# Nutrient_Management_Control_v2_2.net
KiCad netlist of a schematic drawn in EAGLE
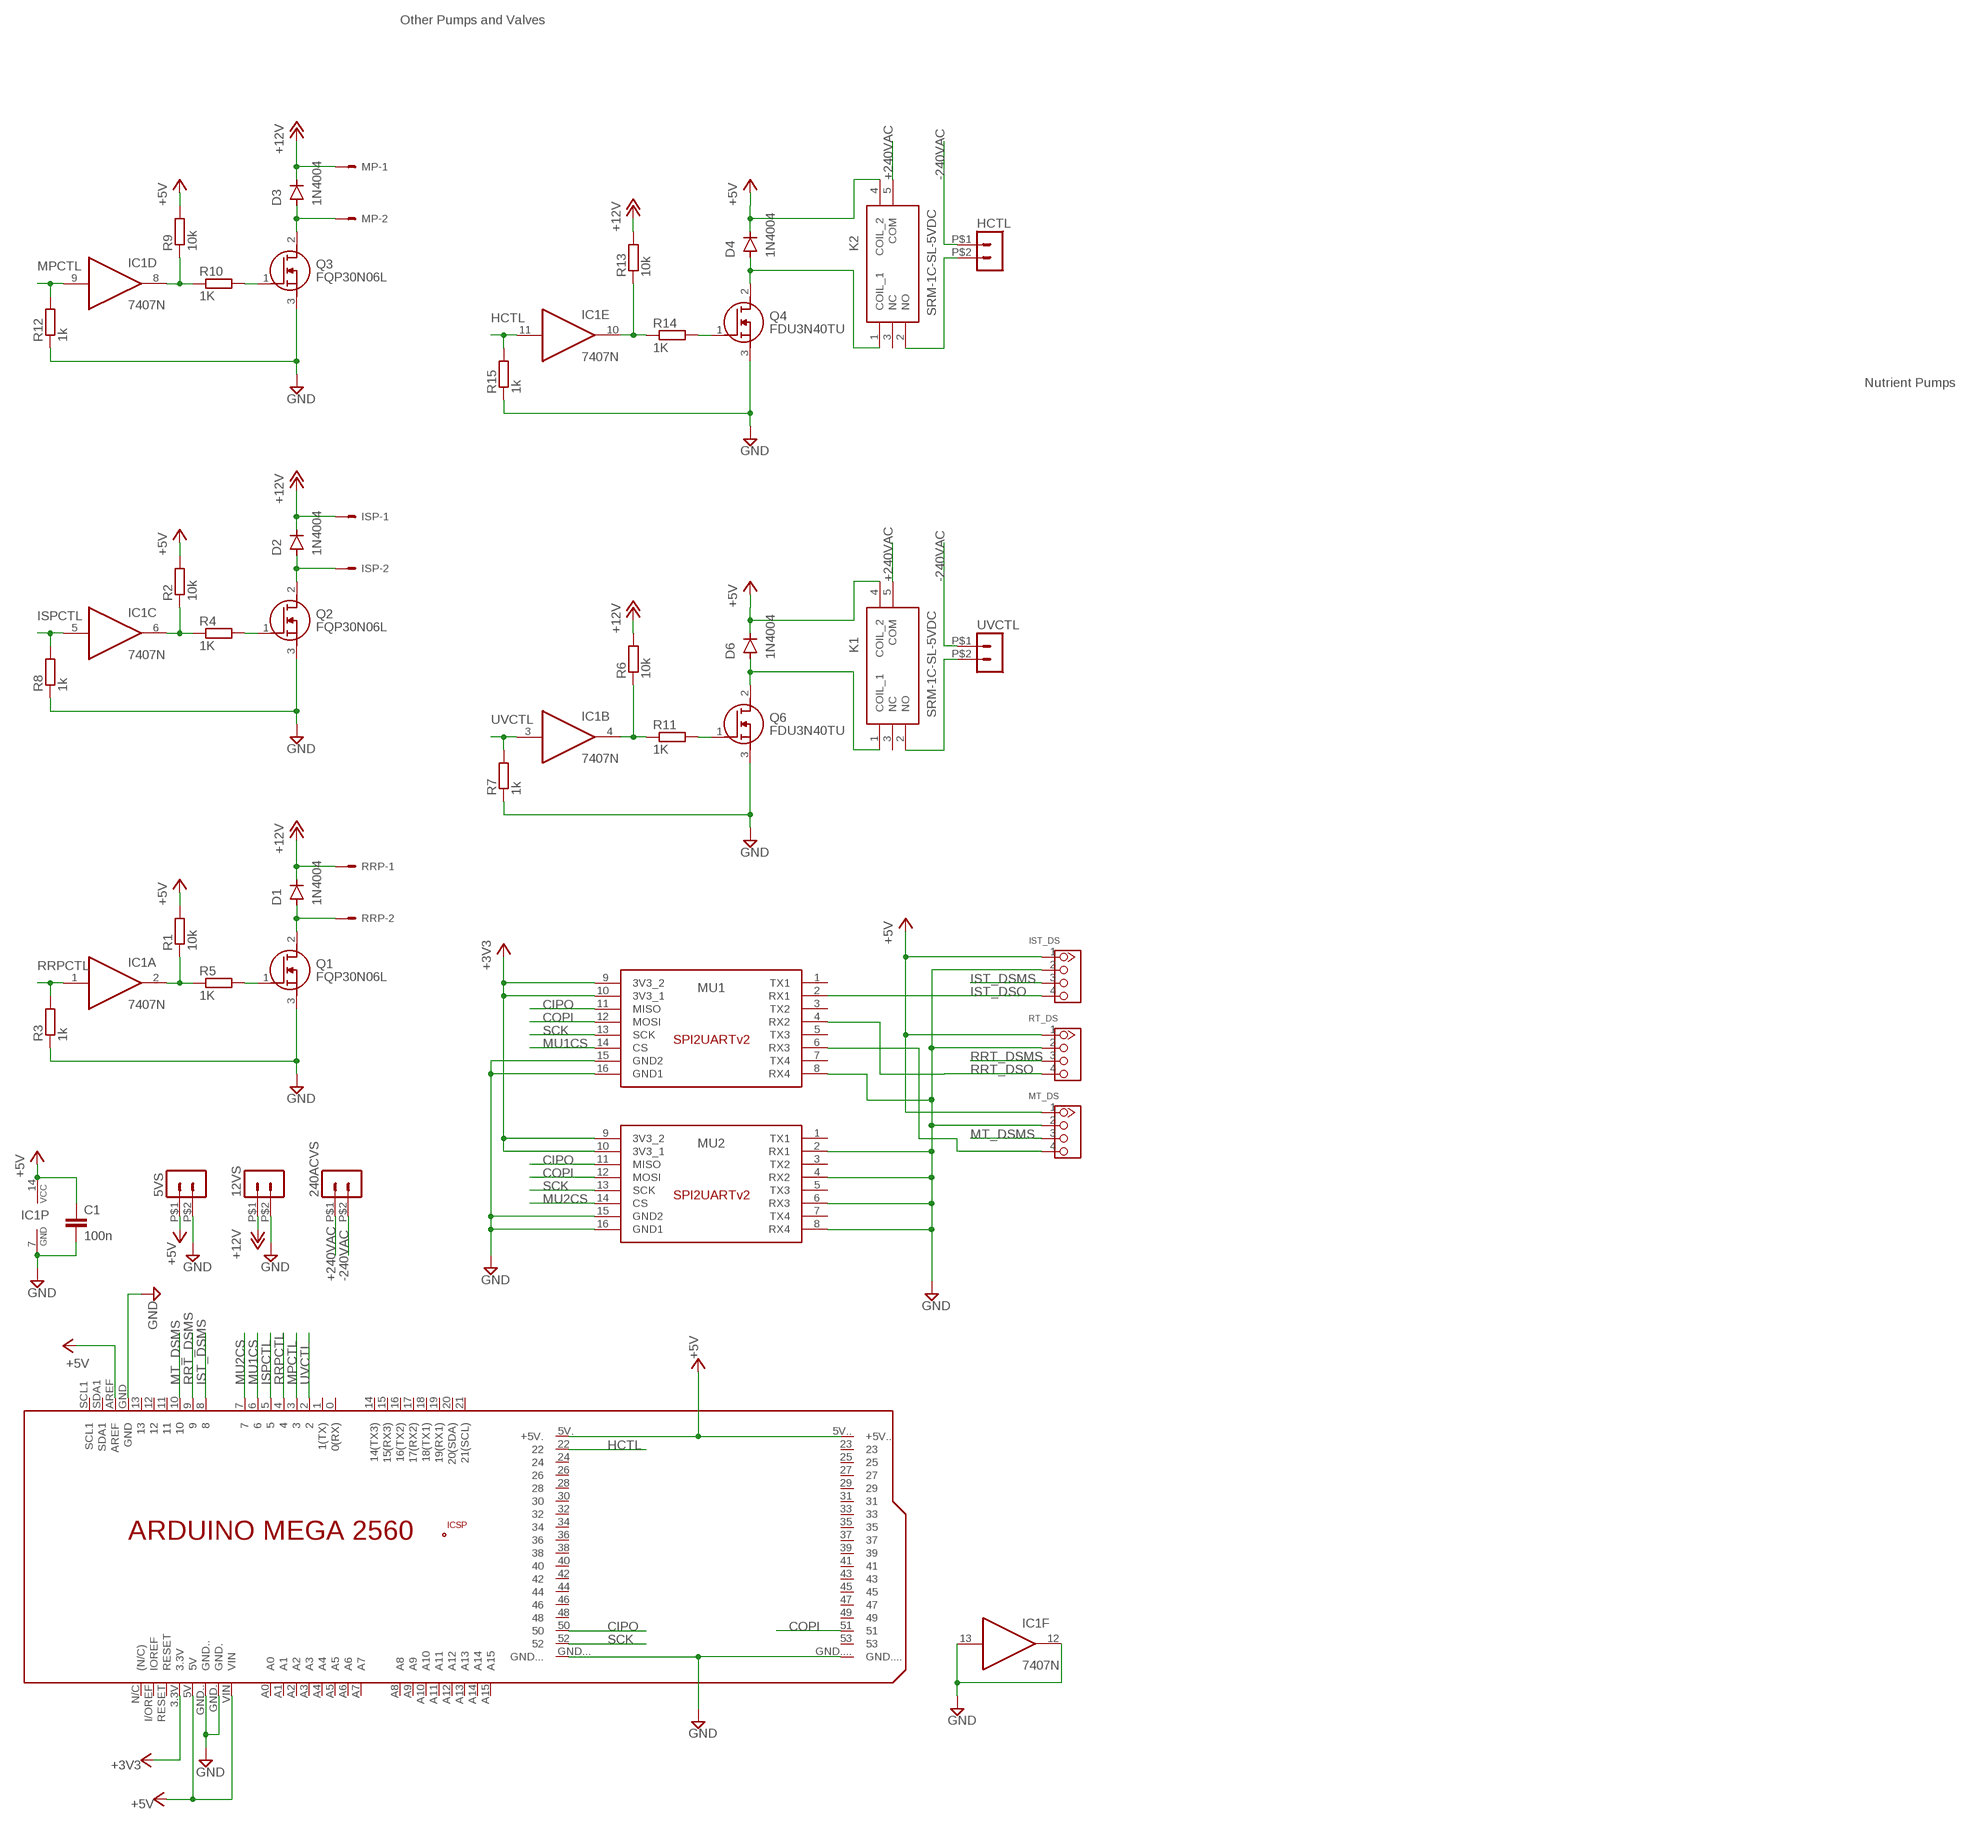
[diagram p0: schematic, sheet 1]

(export (version "E")
  (design (tool "Eeschema 10.0.6"))
  (components
    (comp (ref "5VS")
      (value "HEADER_POS2_43650-0215")
      (footprint "eagle-import:43650-0215")
      (libsource (lib "eagle-import") (part "HEADER_POS2_?43650-0215"))
    )
    (comp (ref "12VS")
      (value "HEADER_POS2_43650-0215")
      (footprint "eagle-import:43650-0215")
      (libsource (lib "eagle-import") (part "HEADER_POS2_?43650-0215"))
    )
    (comp (ref "240ACVS")
      (value "HEADER_POS2_43650-0215")
      (footprint "eagle-import:43650-0215")
      (libsource (lib "eagle-import") (part "HEADER_POS2_?43650-0215"))
    )
    (comp (ref "C1")
      (value "100n")
      (footprint "eagle-import:C050-024X044")
      (libsource (lib "eagle-import") (part "C-EU050-024X044"))
    )
    (comp (ref "D1")
      (value "1N4004")
      (footprint "eagle-import:DO-41")
      (fields
        (field (name "DIGIKEY_PART_NUMBER") "1N4004MSCT-ND")
        (field (name "MANUFACTURER") "Micro Commercial Co")
        (field (name "CREATED_BY") "PCBLayout.com")
      )
      (libsource (lib "eagle-import") (part "1N4004"))
    )
    (comp (ref "D2")
      (value "1N4004")
      (footprint "eagle-import:DO-41")
      (fields
        (field (name "DIGIKEY_PART_NUMBER") "1N4004MSCT-ND")
        (field (name "MANUFACTURER") "Micro Commercial Co")
        (field (name "CREATED_BY") "PCBLayout.com")
      )
      (libsource (lib "eagle-import") (part "1N4004"))
    )
    (comp (ref "D3")
      (value "1N4004")
      (footprint "eagle-import:DO-41")
      (fields
        (field (name "DIGIKEY_PART_NUMBER") "1N4004MSCT-ND")
        (field (name "MANUFACTURER") "Micro Commercial Co")
        (field (name "CREATED_BY") "PCBLayout.com")
      )
      (libsource (lib "eagle-import") (part "1N4004"))
    )
    (comp (ref "D4")
      (value "1N4004")
      (footprint "eagle-import:DO-41")
      (fields
        (field (name "DIGIKEY_PART_NUMBER") "1N4004MSCT-ND")
        (field (name "MANUFACTURER") "Micro Commercial Co")
        (field (name "CREATED_BY") "PCBLayout.com")
      )
      (libsource (lib "eagle-import") (part "1N4004"))
    )
    (comp (ref "D6")
      (value "1N4004")
      (footprint "eagle-import:DO-41")
      (fields
        (field (name "DIGIKEY_PART_NUMBER") "1N4004MSCT-ND")
        (field (name "MANUFACTURER") "Micro Commercial Co")
        (field (name "CREATED_BY") "PCBLayout.com")
      )
      (libsource (lib "eagle-import") (part "1N4004"))
    )
    (comp (ref "HCTL")
      (value "HEADER_POS2_43650-0215")
      (footprint "eagle-import:43650-0215")
      (libsource (lib "eagle-import") (part "HEADER_POS2_?43650-0215"))
    )
    (comp (ref "IC1")
      (value "7407N")
      (footprint "eagle-import:DIL14")
      (libsource (lib "eagle-import") (part "7407N"))
    )
    (comp (ref "ISP")
      (value "JST-XH-02-PIN-LONG-PAD")
      (footprint "eagle-import:JST-XH-02-PACKAGE-LONG-PAD")
      (libsource (lib "eagle-import") (part "JST-XH-02-PIN-LONG-PAD"))
    )
    (comp (ref "IST_DS")
      (value "4P-2.0-90D")
      (footprint "eagle-import:HW4-2.0-90D")
      (libsource (lib "eagle-import") (part "GROVE-CONNECTOR-DIP-90D(4P-2.0)"))
    )
    (comp (ref "K1")
      (value "SRM-1C-SL-5VDC")
      (footprint "eagle-import:SRM1CSL5VDC")
      (libsource (lib "eagle-import") (part "SRM-1C-SL-5VDC"))
    )
    (comp (ref "K2")
      (value "SRM-1C-SL-5VDC")
      (footprint "eagle-import:SRM1CSL5VDC")
      (libsource (lib "eagle-import") (part "SRM-1C-SL-5VDC"))
    )
    (comp (ref "MP")
      (value "JST-XH-02-PIN-LONG-PAD")
      (footprint "eagle-import:JST-XH-02-PACKAGE-LONG-PAD")
      (libsource (lib "eagle-import") (part "JST-XH-02-PIN-LONG-PAD"))
    )
    (comp (ref "MT_DS")
      (value "4P-2.0-90D")
      (footprint "eagle-import:HW4-2.0-90D")
      (libsource (lib "eagle-import") (part "GROVE-CONNECTOR-DIP-90D(4P-2.0)"))
    )
    (comp (ref "MU1")
      (value "SPI2UART_HEADERS")
      (footprint "eagle-import:SPI2UARTV2")
      (libsource (lib "eagle-import") (part "SPI2UART_HEADERS"))
    )
    (comp (ref "MU2")
      (value "SPI2UART_HEADERS")
      (footprint "eagle-import:SPI2UARTV2")
      (libsource (lib "eagle-import") (part "SPI2UART_HEADERS"))
    )
    (comp (ref "PCB2")
      (value "ARDUINO_MEGA2560_SHIELD")
      (footprint "eagle-import:ARDUINO_MEGA2560_SHIELD")
      (libsource (lib "eagle-import") (part "ARDUINO_MEGA2560_SHIELD"))
    )
    (comp (ref "Q1")
      (value "FQP30N06L")
      (footprint "eagle-import:TO254P470X1016X2019-3P")
      (fields (field (name "RS_PART_NUMBER") "8075863P"))
      (libsource (lib "eagle-import") (part "FQP30N06L"))
    )
    (comp (ref "Q2")
      (value "FQP30N06L")
      (footprint "eagle-import:TO254P470X1016X2019-3P")
      (fields (field (name "RS_PART_NUMBER") "8075863P"))
      (libsource (lib "eagle-import") (part "FQP30N06L"))
    )
    (comp (ref "Q3")
      (value "FQP30N06L")
      (footprint "eagle-import:TO254P470X1016X2019-3P")
      (fields (field (name "RS_PART_NUMBER") "8075863P"))
      (libsource (lib "eagle-import") (part "FQP30N06L"))
    )
    (comp (ref "Q4")
      (value "FDU3N40TU")
      (footprint "eagle-import:TO229P250X658X985-3P")
      (fields (field (name "RS_PART_NUMBER") "8070701P"))
      (libsource (lib "eagle-import") (part "FDU3N40TU"))
    )
    (comp (ref "Q6")
      (value "FDU3N40TU")
      (footprint "eagle-import:TO229P250X658X985-3P")
      (fields (field (name "RS_PART_NUMBER") "8070701P"))
      (libsource (lib "eagle-import") (part "FDU3N40TU"))
    )
    (comp (ref "R1")
      (value "10k")
      (footprint "eagle-import:0204_7")
      (libsource (lib "eagle-import") (part "R-EU_0204/7"))
    )
    (comp (ref "R2")
      (value "10k")
      (footprint "eagle-import:0204_7")
      (libsource (lib "eagle-import") (part "R-EU_0204/7"))
    )
    (comp (ref "R3")
      (value "1k")
      (footprint "eagle-import:0204_7")
      (libsource (lib "eagle-import") (part "R-EU_0204/7"))
    )
    (comp (ref "R4")
      (value "1K")
      (footprint "eagle-import:0204_7")
      (libsource (lib "eagle-import") (part "R-EU_0204/7"))
    )
    (comp (ref "R5")
      (value "1K")
      (footprint "eagle-import:0204_7")
      (libsource (lib "eagle-import") (part "R-EU_0204/7"))
    )
    (comp (ref "R6")
      (value "10k")
      (footprint "eagle-import:0204_7")
      (libsource (lib "eagle-import") (part "R-EU_0204/7"))
    )
    (comp (ref "R7")
      (value "1k")
      (footprint "eagle-import:0204_7")
      (libsource (lib "eagle-import") (part "R-EU_0204/7"))
    )
    (comp (ref "R8")
      (value "1k")
      (footprint "eagle-import:0204_7")
      (libsource (lib "eagle-import") (part "R-EU_0204/7"))
    )
    (comp (ref "R9")
      (value "10k")
      (footprint "eagle-import:0204_7")
      (libsource (lib "eagle-import") (part "R-EU_0204/7"))
    )
    (comp (ref "R10")
      (value "1K")
      (footprint "eagle-import:0204_7")
      (libsource (lib "eagle-import") (part "R-EU_0204/7"))
    )
    (comp (ref "R11")
      (value "1K")
      (footprint "eagle-import:0204_7")
      (libsource (lib "eagle-import") (part "R-EU_0204/7"))
    )
    (comp (ref "R12")
      (value "1k")
      (footprint "eagle-import:0204_7")
      (libsource (lib "eagle-import") (part "R-EU_0204/7"))
    )
    (comp (ref "R13")
      (value "10k")
      (footprint "eagle-import:0204_7")
      (libsource (lib "eagle-import") (part "R-EU_0204/7"))
    )
    (comp (ref "R14")
      (value "1K")
      (footprint "eagle-import:0204_7")
      (libsource (lib "eagle-import") (part "R-EU_0204/7"))
    )
    (comp (ref "R15")
      (value "1k")
      (footprint "eagle-import:0204_7")
      (libsource (lib "eagle-import") (part "R-EU_0204/7"))
    )
    (comp (ref "RRP")
      (value "JST-XH-02-PIN-LONG-PAD")
      (footprint "eagle-import:JST-XH-02-PACKAGE-LONG-PAD")
      (libsource (lib "eagle-import") (part "JST-XH-02-PIN-LONG-PAD"))
    )
    (comp (ref "RT_DS")
      (value "4P-2.0-90D")
      (footprint "eagle-import:HW4-2.0-90D")
      (libsource (lib "eagle-import") (part "GROVE-CONNECTOR-DIP-90D(4P-2.0)"))
    )
    (comp (ref "UVCTL")
      (value "HEADER_POS2_43650-0215")
      (footprint "eagle-import:43650-0215")
      (libsource (lib "eagle-import") (part "HEADER_POS2_?43650-0215"))
    )
  )
  (nets
    (net (code "1") (name "+3V3") (class "Default")
      (node (ref "MU1") (pin "10") (pinfunction "3V3_1_10") (pintype "power_in"))
      (node (ref "MU1") (pin "9") (pinfunction "3V3_2_9") (pintype "power_in"))
      (node (ref "MU2") (pin "10") (pinfunction "3V3_1_10") (pintype "power_in"))
      (node (ref "MU2") (pin "9") (pinfunction "3V3_2_9") (pintype "power_in"))
      (node (ref "PCB2") (pin "3.3V") (pinfunction "3.3V_3.3V") (pintype "bidirectional"))
    )
    (net (code "2") (name "+5V") (class "Default")
      (node (ref "5VS") (pin "P$1") (pinfunction "1_P$1") (pintype "passive"))
      (node (ref "C1") (pin "1") (pinfunction "1_1") (pintype "passive"))
      (node (ref "D4") (pin "C") (pinfunction "C_C") (pintype "passive"))
      (node (ref "D6") (pin "C") (pinfunction "C_C") (pintype "passive"))
      (node (ref "IC1") (pin "14") (pinfunction "VCC_14") (pintype "power_in"))
      (node (ref "IST_DS") (pin "1") (pinfunction "1_1") (pintype "bidirectional"))
      (node (ref "K1") (pin "4") (pinfunction "COIL_2_4") (pintype "bidirectional"))
      (node (ref "K2") (pin "4") (pinfunction "COIL_2_4") (pintype "bidirectional"))
      (node (ref "MT_DS") (pin "1") (pinfunction "1_1") (pintype "bidirectional"))
      (node (ref "PCB2") (pin "5V") (pinfunction "5V_5V") (pintype "bidirectional"))
      (node (ref "PCB2") (pin "5V.") (pinfunction "+5V._5V.") (pintype "bidirectional"))
      (node (ref "PCB2") (pin "5V..") (pinfunction "+5V.._5V..") (pintype "bidirectional"))
      (node (ref "PCB2") (pin "AREF") (pinfunction "AREF_AREF") (pintype "bidirectional"))
      (node (ref "PCB2") (pin "VIN") (pinfunction "VIN_VIN") (pintype "bidirectional"))
      (node (ref "R1") (pin "2") (pinfunction "2_2") (pintype "passive"))
      (node (ref "R2") (pin "2") (pinfunction "2_2") (pintype "passive"))
      (node (ref "R9") (pin "2") (pinfunction "2_2") (pintype "passive"))
      (node (ref "RT_DS") (pin "1") (pinfunction "1_1") (pintype "bidirectional"))
    )
    (net (code "3") (name "+12V") (class "Default")
      (node (ref "12VS") (pin "P$1") (pinfunction "1_P$1") (pintype "passive"))
      (node (ref "D1") (pin "C") (pinfunction "C_C") (pintype "passive"))
      (node (ref "D2") (pin "C") (pinfunction "C_C") (pintype "passive"))
      (node (ref "D3") (pin "C") (pinfunction "C_C") (pintype "passive"))
      (node (ref "ISP") (pin "1") (pinfunction "S_1") (pintype "passive"))
      (node (ref "MP") (pin "1") (pinfunction "S_1") (pintype "passive"))
      (node (ref "R13") (pin "2") (pinfunction "2_2") (pintype "passive"))
      (node (ref "R6") (pin "2") (pinfunction "2_2") (pintype "passive"))
      (node (ref "RRP") (pin "1") (pinfunction "S_1") (pintype "passive"))
    )
    (net (code "4") (name "/+240VAC") (class "Default")
      (node (ref "240ACVS") (pin "P$1") (pinfunction "1_P$1") (pintype "passive"))
      (node (ref "K1") (pin "5") (pinfunction "COM_5") (pintype "bidirectional"))
      (node (ref "K2") (pin "5") (pinfunction "COM_5") (pintype "bidirectional"))
    )
    (net (code "5") (name "/-240VAC") (class "Default")
      (node (ref "240ACVS") (pin "P$2") (pinfunction "2_P$2") (pintype "passive"))
      (node (ref "HCTL") (pin "P$1") (pinfunction "1_P$1") (pintype "passive"))
      (node (ref "UVCTL") (pin "P$1") (pinfunction "1_P$1") (pintype "passive"))
    )
    (net (code "6") (name "/CIPO") (class "Default")
      (node (ref "MU1") (pin "11") (pinfunction "MISO_11") (pintype "output"))
      (node (ref "MU2") (pin "11") (pinfunction "MISO_11") (pintype "output"))
      (node (ref "PCB2") (pin "50") (pinfunction "50_50") (pintype "bidirectional"))
    )
    (net (code "7") (name "/COPI") (class "Default")
      (node (ref "MU1") (pin "12") (pinfunction "MOSI_12") (pintype "input"))
      (node (ref "MU2") (pin "12") (pinfunction "MOSI_12") (pintype "input"))
      (node (ref "PCB2") (pin "51") (pinfunction "51_51") (pintype "bidirectional"))
    )
    (net (code "8") (name "/HCTL") (class "Default")
      (node (ref "IC1") (pin "11") (pinfunction "I_11") (pintype "input"))
      (node (ref "PCB2") (pin "22") (pinfunction "22_22") (pintype "bidirectional"))
      (node (ref "R15") (pin "2") (pinfunction "2_2") (pintype "passive"))
    )
    (net (code "9") (name "/ISPCTL") (class "Default")
      (node (ref "IC1") (pin "5") (pinfunction "I_5") (pintype "input"))
      (node (ref "PCB2") (pin "5") (pinfunction "5_5") (pintype "bidirectional"))
      (node (ref "R8") (pin "2") (pinfunction "2_2") (pintype "passive"))
    )
    (net (code "10") (name "/IST_DSMS") (class "Default")
      (node (ref "IST_DS") (pin "3") (pinfunction "3_3") (pintype "bidirectional"))
      (node (ref "PCB2") (pin "8") (pinfunction "8_8") (pintype "bidirectional"))
    )
    (net (code "11") (name "/IST_DSO") (class "Default")
      (node (ref "IST_DS") (pin "4") (pinfunction "4_4") (pintype "bidirectional"))
      (node (ref "MU1") (pin "2") (pinfunction "RX1_2") (pintype "input"))
    )
    (net (code "12") (name "/MPCTL") (class "Default")
      (node (ref "IC1") (pin "9") (pinfunction "I_9") (pintype "input"))
      (node (ref "PCB2") (pin "3") (pinfunction "3_3") (pintype "bidirectional"))
      (node (ref "R12") (pin "2") (pinfunction "2_2") (pintype "passive"))
    )
    (net (code "13") (name "/MT_DSMS") (class "Default")
      (node (ref "MT_DS") (pin "3") (pinfunction "3_3") (pintype "bidirectional"))
      (node (ref "PCB2") (pin "10") (pinfunction "10_10") (pintype "bidirectional"))
    )
    (net (code "14") (name "/MU1CS") (class "Default")
      (node (ref "MU1") (pin "14") (pinfunction "CS_14") (pintype "input"))
      (node (ref "PCB2") (pin "6") (pinfunction "6_6") (pintype "bidirectional"))
    )
    (net (code "15") (name "/MU2CS") (class "Default")
      (node (ref "MU2") (pin "14") (pinfunction "CS_14") (pintype "input"))
      (node (ref "PCB2") (pin "7") (pinfunction "7_7") (pintype "bidirectional"))
    )
    (net (code "16") (name "/RRPCTL") (class "Default")
      (node (ref "IC1") (pin "1") (pinfunction "I_1") (pintype "input"))
      (node (ref "PCB2") (pin "4") (pinfunction "4_4") (pintype "bidirectional"))
      (node (ref "R3") (pin "2") (pinfunction "2_2") (pintype "passive"))
    )
    (net (code "17") (name "/RRT_DSMS") (class "Default")
      (node (ref "PCB2") (pin "9") (pinfunction "9_9") (pintype "bidirectional"))
      (node (ref "RT_DS") (pin "3") (pinfunction "3_3") (pintype "bidirectional"))
    )
    (net (code "18") (name "/RRT_DSO") (class "Default")
      (node (ref "MU1") (pin "4") (pinfunction "RX2_4") (pintype "input"))
      (node (ref "RT_DS") (pin "4") (pinfunction "4_4") (pintype "bidirectional"))
    )
    (net (code "19") (name "/SCK") (class "Default")
      (node (ref "MU1") (pin "13") (pinfunction "SCK_13") (pintype "input"))
      (node (ref "MU2") (pin "13") (pinfunction "SCK_13") (pintype "input"))
      (node (ref "PCB2") (pin "52") (pinfunction "52_52") (pintype "bidirectional"))
    )
    (net (code "20") (name "/UVCTL") (class "Default")
      (node (ref "IC1") (pin "3") (pinfunction "I_3") (pintype "input"))
      (node (ref "PCB2") (pin "2") (pinfunction "2_2") (pintype "bidirectional"))
      (node (ref "R7") (pin "2") (pinfunction "2_2") (pintype "passive"))
    )
    (net (code "21") (name "GND") (class "Default")
      (node (ref "12VS") (pin "P$2") (pinfunction "2_P$2") (pintype "passive"))
      (node (ref "5VS") (pin "P$2") (pinfunction "2_P$2") (pintype "passive"))
      (node (ref "C1") (pin "2") (pinfunction "2_2") (pintype "passive"))
      (node (ref "IC1") (pin "12") (pinfunction "O_12") (pintype "open_collector"))
      (node (ref "IC1") (pin "13") (pinfunction "I_13") (pintype "input"))
      (node (ref "IC1") (pin "7") (pinfunction "GND_7") (pintype "power_in"))
      (node (ref "IST_DS") (pin "2") (pinfunction "2_2") (pintype "bidirectional"))
      (node (ref "MT_DS") (pin "2") (pinfunction "2_2") (pintype "bidirectional"))
      (node (ref "MU1") (pin "15") (pinfunction "GND2_15") (pintype "power_in"))
      (node (ref "MU1") (pin "16") (pinfunction "GND1_16") (pintype "power_in"))
      (node (ref "MU1") (pin "8") (pinfunction "RX4_8") (pintype "input"))
      (node (ref "MU2") (pin "15") (pinfunction "GND2_15") (pintype "power_in"))
      (node (ref "MU2") (pin "16") (pinfunction "GND1_16") (pintype "power_in"))
      (node (ref "MU2") (pin "2") (pinfunction "RX1_2") (pintype "input"))
      (node (ref "MU2") (pin "4") (pinfunction "RX2_4") (pintype "input"))
      (node (ref "MU2") (pin "6") (pinfunction "RX3_6") (pintype "input"))
      (node (ref "MU2") (pin "8") (pinfunction "RX4_8") (pintype "input"))
      (node (ref "PCB2") (pin "GND") (pinfunction "GND_GND") (pintype "bidirectional"))
      (node (ref "PCB2") (pin "GND.") (pinfunction "GND._GND.") (pintype "bidirectional"))
      (node (ref "PCB2") (pin "GND..") (pinfunction "GND.._GND..") (pintype "bidirectional"))
      (node (ref "PCB2") (pin "GND...") (pinfunction "GND..._GND...") (pintype "bidirectional"))
      (node (ref "PCB2") (pin "GND....") (pinfunction "GND...._GND....") (pintype "bidirectional"))
      (node (ref "Q1") (pin "3") (pinfunction "S_3") (pintype "bidirectional"))
      (node (ref "Q2") (pin "3") (pinfunction "S_3") (pintype "bidirectional"))
      (node (ref "Q3") (pin "3") (pinfunction "S_3") (pintype "bidirectional"))
      (node (ref "Q4") (pin "3") (pinfunction "S_3") (pintype "bidirectional"))
      (node (ref "Q6") (pin "3") (pinfunction "S_3") (pintype "bidirectional"))
      (node (ref "R12") (pin "1") (pinfunction "1_1") (pintype "passive"))
      (node (ref "R15") (pin "1") (pinfunction "1_1") (pintype "passive"))
      (node (ref "R3") (pin "1") (pinfunction "1_1") (pintype "passive"))
      (node (ref "R7") (pin "1") (pinfunction "1_1") (pintype "passive"))
      (node (ref "R8") (pin "1") (pinfunction "1_1") (pintype "passive"))
      (node (ref "RT_DS") (pin "2") (pinfunction "2_2") (pintype "bidirectional"))
    )
    (net (code "22") (name "Net-(HCTL-2)") (class "Default")
      (node (ref "HCTL") (pin "P$2") (pinfunction "2_P$2") (pintype "passive"))
      (node (ref "K2") (pin "2") (pinfunction "NO_2") (pintype "bidirectional"))
    )
    (net (code "23") (name "Net-(IC1A-O)") (class "Default")
      (node (ref "IC1") (pin "2") (pinfunction "O_2") (pintype "open_collector"))
      (node (ref "R1") (pin "1") (pinfunction "1_1") (pintype "passive"))
      (node (ref "R5") (pin "1") (pinfunction "1_1") (pintype "passive"))
    )
    (net (code "24") (name "Net-(IC1B-O)") (class "Default")
      (node (ref "IC1") (pin "4") (pinfunction "O_4") (pintype "open_collector"))
      (node (ref "R11") (pin "1") (pinfunction "1_1") (pintype "passive"))
      (node (ref "R6") (pin "1") (pinfunction "1_1") (pintype "passive"))
    )
    (net (code "25") (name "Net-(IC1C-O)") (class "Default")
      (node (ref "IC1") (pin "6") (pinfunction "O_6") (pintype "open_collector"))
      (node (ref "R2") (pin "1") (pinfunction "1_1") (pintype "passive"))
      (node (ref "R4") (pin "1") (pinfunction "1_1") (pintype "passive"))
    )
    (net (code "26") (name "Net-(IC1D-O)") (class "Default")
      (node (ref "IC1") (pin "8") (pinfunction "O_8") (pintype "open_collector"))
      (node (ref "R10") (pin "1") (pinfunction "1_1") (pintype "passive"))
      (node (ref "R9") (pin "1") (pinfunction "1_1") (pintype "passive"))
    )
    (net (code "27") (name "Net-(IC1E-O)") (class "Default")
      (node (ref "IC1") (pin "10") (pinfunction "O_10") (pintype "open_collector"))
      (node (ref "R13") (pin "1") (pinfunction "1_1") (pintype "passive"))
      (node (ref "R14") (pin "1") (pinfunction "1_1") (pintype "passive"))
    )
    (net (code "28") (name "Net-(ISPB-S)") (class "Default")
      (node (ref "D2") (pin "A") (pinfunction "A_A") (pintype "passive"))
      (node (ref "ISP") (pin "2") (pinfunction "S_2") (pintype "passive"))
      (node (ref "Q2") (pin "2") (pinfunction "D_2") (pintype "bidirectional"))
    )
    (net (code "29") (name "Net-(K1-COIL_1)") (class "Default")
      (node (ref "D6") (pin "A") (pinfunction "A_A") (pintype "passive"))
      (node (ref "K1") (pin "1") (pinfunction "COIL_1_1") (pintype "bidirectional"))
      (node (ref "Q6") (pin "2") (pinfunction "D_2") (pintype "bidirectional"))
    )
    (net (code "30") (name "Net-(K1-NO)") (class "Default")
      (node (ref "K1") (pin "2") (pinfunction "NO_2") (pintype "bidirectional"))
      (node (ref "UVCTL") (pin "P$2") (pinfunction "2_P$2") (pintype "passive"))
    )
    (net (code "31") (name "Net-(K2-COIL_1)") (class "Default")
      (node (ref "D4") (pin "A") (pinfunction "A_A") (pintype "passive"))
      (node (ref "K2") (pin "1") (pinfunction "COIL_1_1") (pintype "bidirectional"))
      (node (ref "Q4") (pin "2") (pinfunction "D_2") (pintype "bidirectional"))
    )
    (net (code "32") (name "Net-(MPB-S)") (class "Default")
      (node (ref "D3") (pin "A") (pinfunction "A_A") (pintype "passive"))
      (node (ref "MP") (pin "2") (pinfunction "S_2") (pintype "passive"))
      (node (ref "Q3") (pin "2") (pinfunction "D_2") (pintype "bidirectional"))
    )
    (net (code "33") (name "Net-(MU1-RX3)") (class "Default")
      (node (ref "MT_DS") (pin "4") (pinfunction "4_4") (pintype "bidirectional"))
      (node (ref "MU1") (pin "6") (pinfunction "RX3_6") (pintype "input"))
    )
    (net (code "34") (name "Net-(Q1-D)") (class "Default")
      (node (ref "D1") (pin "A") (pinfunction "A_A") (pintype "passive"))
      (node (ref "Q1") (pin "2") (pinfunction "D_2") (pintype "bidirectional"))
      (node (ref "RRP") (pin "2") (pinfunction "S_2") (pintype "passive"))
    )
    (net (code "35") (name "Net-(Q1-G)") (class "Default")
      (node (ref "Q1") (pin "1") (pinfunction "G_1") (pintype "bidirectional"))
      (node (ref "R5") (pin "2") (pinfunction "2_2") (pintype "passive"))
    )
    (net (code "36") (name "Net-(Q2-G)") (class "Default")
      (node (ref "Q2") (pin "1") (pinfunction "G_1") (pintype "bidirectional"))
      (node (ref "R4") (pin "2") (pinfunction "2_2") (pintype "passive"))
    )
    (net (code "37") (name "Net-(Q3-G)") (class "Default")
      (node (ref "Q3") (pin "1") (pinfunction "G_1") (pintype "bidirectional"))
      (node (ref "R10") (pin "2") (pinfunction "2_2") (pintype "passive"))
    )
    (net (code "38") (name "Net-(Q4-G)") (class "Default")
      (node (ref "Q4") (pin "1") (pinfunction "G_1") (pintype "bidirectional"))
      (node (ref "R14") (pin "2") (pinfunction "2_2") (pintype "passive"))
    )
    (net (code "39") (name "Net-(Q6-G)") (class "Default")
      (node (ref "Q6") (pin "1") (pinfunction "G_1") (pintype "bidirectional"))
      (node (ref "R11") (pin "2") (pinfunction "2_2") (pintype "passive"))
    )
    (net (code "40") (name "unconnected-(K1-NC-Pad3)") (class "Default")
      (node (ref "K1") (pin "3") (pinfunction "NC_3") (pintype "no_connect"))
    )
    (net (code "41") (name "unconnected-(K2-NC-Pad3)") (class "Default")
      (node (ref "K2") (pin "3") (pinfunction "NC_3") (pintype "no_connect"))
    )
    (net (code "42") (name "unconnected-(MU1-TX1-Pad1)") (class "Default")
      (node (ref "MU1") (pin "1") (pinfunction "TX1_1") (pintype "output"))
    )
    (net (code "43") (name "unconnected-(MU1-TX2-Pad3)") (class "Default")
      (node (ref "MU1") (pin "3") (pinfunction "TX2_3") (pintype "output"))
    )
    (net (code "44") (name "unconnected-(MU1-TX3-Pad5)") (class "Default")
      (node (ref "MU1") (pin "5") (pinfunction "TX3_5") (pintype "output"))
    )
    (net (code "45") (name "unconnected-(MU1-TX4-Pad7)") (class "Default")
      (node (ref "MU1") (pin "7") (pinfunction "TX4_7") (pintype "output"))
    )
    (net (code "46") (name "unconnected-(MU2-TX1-Pad1)") (class "Default")
      (node (ref "MU2") (pin "1") (pinfunction "TX1_1") (pintype "output"))
    )
    (net (code "47") (name "unconnected-(MU2-TX2-Pad3)") (class "Default")
      (node (ref "MU2") (pin "3") (pinfunction "TX2_3") (pintype "output"))
    )
    (net (code "48") (name "unconnected-(MU2-TX3-Pad5)") (class "Default")
      (node (ref "MU2") (pin "5") (pinfunction "TX3_5") (pintype "output"))
    )
    (net (code "49") (name "unconnected-(MU2-TX4-Pad7)") (class "Default")
      (node (ref "MU2") (pin "7") (pinfunction "TX4_7") (pintype "output"))
    )
    (net (code "50") (name "unconnected-(PCB2-(N{slash}C)-PadN{slash}C)") (class "Default")
      (node (ref "PCB2") (pin "N/C") (pinfunction "(N/C)_N/C") (pintype "bidirectional"))
    )
    (net (code "51") (name "unconnected-(PCB2-0(RX)-Pad0)") (class "Default")
      (node (ref "PCB2") (pin "0") (pinfunction "0(RX)_0") (pintype "bidirectional"))
    )
    (net (code "52") (name "unconnected-(PCB2-1(TX)-Pad1)") (class "Default")
      (node (ref "PCB2") (pin "1") (pinfunction "1(TX)_1") (pintype "bidirectional"))
    )
    (net (code "53") (name "unconnected-(PCB2-14(TX3)-Pad14)") (class "Default")
      (node (ref "PCB2") (pin "14") (pinfunction "14(TX3)_14") (pintype "bidirectional"))
    )
    (net (code "54") (name "unconnected-(PCB2-15(RX3)-Pad15)") (class "Default")
      (node (ref "PCB2") (pin "15") (pinfunction "15(RX3)_15") (pintype "bidirectional"))
    )
    (net (code "55") (name "unconnected-(PCB2-16(TX2)-Pad16)") (class "Default")
      (node (ref "PCB2") (pin "16") (pinfunction "16(TX2)_16") (pintype "bidirectional"))
    )
    (net (code "56") (name "unconnected-(PCB2-17(RX2)-Pad17)") (class "Default")
      (node (ref "PCB2") (pin "17") (pinfunction "17(RX2)_17") (pintype "bidirectional"))
    )
    (net (code "57") (name "unconnected-(PCB2-18(TX1)-Pad18)") (class "Default")
      (node (ref "PCB2") (pin "18") (pinfunction "18(TX1)_18") (pintype "bidirectional"))
    )
    (net (code "58") (name "unconnected-(PCB2-19(RX1)-Pad19)") (class "Default")
      (node (ref "PCB2") (pin "19") (pinfunction "19(RX1)_19") (pintype "bidirectional"))
    )
    (net (code "59") (name "unconnected-(PCB2-20(SDA)-Pad20)") (class "Default")
      (node (ref "PCB2") (pin "20") (pinfunction "20(SDA)_20") (pintype "bidirectional"))
    )
    (net (code "60") (name "unconnected-(PCB2-21(SCL)-Pad21)") (class "Default")
      (node (ref "PCB2") (pin "21") (pinfunction "21(SCL)_21") (pintype "bidirectional"))
    )
    (net (code "61") (name "unconnected-(PCB2-IOREF-PadI{slash}OREF)") (class "Default")
      (node (ref "PCB2") (pin "I/OREF") (pinfunction "IOREF_I/OREF") (pintype "bidirectional"))
    )
    (net (code "62") (name "unconnected-(PCB2-Pad+5V_)") (class "Default")
      (node (ref "PCB2") (pin "+5V_") (pinfunction "+5V__+5V_") (pintype "bidirectional"))
    )
    (net (code "63") (name "unconnected-(PCB2-Pad11)") (class "Default")
      (node (ref "PCB2") (pin "11") (pinfunction "11_11") (pintype "bidirectional"))
    )
    (net (code "64") (name "unconnected-(PCB2-Pad12)") (class "Default")
      (node (ref "PCB2") (pin "12") (pinfunction "12_12") (pintype "bidirectional"))
    )
    (net (code "65") (name "unconnected-(PCB2-Pad13)") (class "Default")
      (node (ref "PCB2") (pin "13") (pinfunction "13_13") (pintype "bidirectional"))
    )
    (net (code "66") (name "unconnected-(PCB2-Pad23)") (class "Default")
      (node (ref "PCB2") (pin "23") (pinfunction "23_23") (pintype "bidirectional"))
    )
    (net (code "67") (name "unconnected-(PCB2-Pad24)") (class "Default")
      (node (ref "PCB2") (pin "24") (pinfunction "24_24") (pintype "bidirectional"))
    )
    (net (code "68") (name "unconnected-(PCB2-Pad25)") (class "Default")
      (node (ref "PCB2") (pin "25") (pinfunction "25_25") (pintype "bidirectional"))
    )
    (net (code "69") (name "unconnected-(PCB2-Pad26)") (class "Default")
      (node (ref "PCB2") (pin "26") (pinfunction "26_26") (pintype "bidirectional"))
    )
    (net (code "70") (name "unconnected-(PCB2-Pad27)") (class "Default")
      (node (ref "PCB2") (pin "27") (pinfunction "27_27") (pintype "bidirectional"))
    )
    (net (code "71") (name "unconnected-(PCB2-Pad28)") (class "Default")
      (node (ref "PCB2") (pin "28") (pinfunction "28_28") (pintype "bidirectional"))
    )
    (net (code "72") (name "unconnected-(PCB2-Pad29)") (class "Default")
      (node (ref "PCB2") (pin "29") (pinfunction "29_29") (pintype "bidirectional"))
    )
    (net (code "73") (name "unconnected-(PCB2-Pad30)") (class "Default")
      (node (ref "PCB2") (pin "30") (pinfunction "30_30") (pintype "bidirectional"))
    )
    (net (code "74") (name "unconnected-(PCB2-Pad31)") (class "Default")
      (node (ref "PCB2") (pin "31") (pinfunction "31_31") (pintype "bidirectional"))
    )
    (net (code "75") (name "unconnected-(PCB2-Pad32)") (class "Default")
      (node (ref "PCB2") (pin "32") (pinfunction "32_32") (pintype "bidirectional"))
    )
    (net (code "76") (name "unconnected-(PCB2-Pad33)") (class "Default")
      (node (ref "PCB2") (pin "33") (pinfunction "33_33") (pintype "bidirectional"))
    )
    (net (code "77") (name "unconnected-(PCB2-Pad34)") (class "Default")
      (node (ref "PCB2") (pin "34") (pinfunction "34_34") (pintype "bidirectional"))
    )
    (net (code "78") (name "unconnected-(PCB2-Pad35)") (class "Default")
      (node (ref "PCB2") (pin "35") (pinfunction "35_35") (pintype "bidirectional"))
    )
    (net (code "79") (name "unconnected-(PCB2-Pad36)") (class "Default")
      (node (ref "PCB2") (pin "36") (pinfunction "36_36") (pintype "bidirectional"))
    )
    (net (code "80") (name "unconnected-(PCB2-Pad37)") (class "Default")
      (node (ref "PCB2") (pin "37") (pinfunction "37_37") (pintype "bidirectional"))
    )
    (net (code "81") (name "unconnected-(PCB2-Pad38)") (class "Default")
      (node (ref "PCB2") (pin "38") (pinfunction "38_38") (pintype "bidirectional"))
    )
    (net (code "82") (name "unconnected-(PCB2-Pad39)") (class "Default")
      (node (ref "PCB2") (pin "39") (pinfunction "39_39") (pintype "bidirectional"))
    )
    (net (code "83") (name "unconnected-(PCB2-Pad40)") (class "Default")
      (node (ref "PCB2") (pin "40") (pinfunction "40_40") (pintype "bidirectional"))
    )
    (net (code "84") (name "unconnected-(PCB2-Pad41)") (class "Default")
      (node (ref "PCB2") (pin "41") (pinfunction "41_41") (pintype "bidirectional"))
    )
    (net (code "85") (name "unconnected-(PCB2-Pad42)") (class "Default")
      (node (ref "PCB2") (pin "42") (pinfunction "42_42") (pintype "bidirectional"))
    )
    (net (code "86") (name "unconnected-(PCB2-Pad43)") (class "Default")
      (node (ref "PCB2") (pin "43") (pinfunction "43_43") (pintype "bidirectional"))
    )
    (net (code "87") (name "unconnected-(PCB2-Pad44)") (class "Default")
      (node (ref "PCB2") (pin "44") (pinfunction "44_44") (pintype "bidirectional"))
    )
    (net (code "88") (name "unconnected-(PCB2-Pad45)") (class "Default")
      (node (ref "PCB2") (pin "45") (pinfunction "45_45") (pintype "bidirectional"))
    )
    (net (code "89") (name "unconnected-(PCB2-Pad46)") (class "Default")
      (node (ref "PCB2") (pin "46") (pinfunction "46_46") (pintype "bidirectional"))
    )
    (net (code "90") (name "unconnected-(PCB2-Pad47)") (class "Default")
      (node (ref "PCB2") (pin "47") (pinfunction "47_47") (pintype "bidirectional"))
    )
    (net (code "91") (name "unconnected-(PCB2-Pad48)") (class "Default")
      (node (ref "PCB2") (pin "48") (pinfunction "48_48") (pintype "bidirectional"))
    )
    (net (code "92") (name "unconnected-(PCB2-Pad49)") (class "Default")
      (node (ref "PCB2") (pin "49") (pinfunction "49_49") (pintype "bidirectional"))
    )
    (net (code "93") (name "unconnected-(PCB2-Pad53)") (class "Default")
      (node (ref "PCB2") (pin "53") (pinfunction "53_53") (pintype "bidirectional"))
    )
    (net (code "94") (name "unconnected-(PCB2-PadA0)") (class "Default")
      (node (ref "PCB2") (pin "A0") (pinfunction "A0_A0") (pintype "bidirectional"))
    )
    (net (code "95") (name "unconnected-(PCB2-PadA1)") (class "Default")
      (node (ref "PCB2") (pin "A1") (pinfunction "A1_A1") (pintype "bidirectional"))
    )
    (net (code "96") (name "unconnected-(PCB2-PadA2)") (class "Default")
      (node (ref "PCB2") (pin "A2") (pinfunction "A2_A2") (pintype "bidirectional"))
    )
    (net (code "97") (name "unconnected-(PCB2-PadA3)") (class "Default")
      (node (ref "PCB2") (pin "A3") (pinfunction "A3_A3") (pintype "bidirectional"))
    )
    (net (code "98") (name "unconnected-(PCB2-PadA4)") (class "Default")
      (node (ref "PCB2") (pin "A4") (pinfunction "A4_A4") (pintype "bidirectional"))
    )
    (net (code "99") (name "unconnected-(PCB2-PadA5)") (class "Default")
      (node (ref "PCB2") (pin "A5") (pinfunction "A5_A5") (pintype "bidirectional"))
    )
    (net (code "100") (name "unconnected-(PCB2-PadA6)") (class "Default")
      (node (ref "PCB2") (pin "A6") (pinfunction "A6_A6") (pintype "bidirectional"))
    )
    (net (code "101") (name "unconnected-(PCB2-PadA7)") (class "Default")
      (node (ref "PCB2") (pin "A7") (pinfunction "A7_A7") (pintype "bidirectional"))
    )
    (net (code "102") (name "unconnected-(PCB2-PadA8)") (class "Default")
      (node (ref "PCB2") (pin "A8") (pinfunction "A8_A8") (pintype "bidirectional"))
    )
    (net (code "103") (name "unconnected-(PCB2-PadA9)") (class "Default")
      (node (ref "PCB2") (pin "A9") (pinfunction "A9_A9") (pintype "bidirectional"))
    )
    (net (code "104") (name "unconnected-(PCB2-PadA10)") (class "Default")
      (node (ref "PCB2") (pin "A10") (pinfunction "A10_A10") (pintype "bidirectional"))
    )
    (net (code "105") (name "unconnected-(PCB2-PadA11)") (class "Default")
      (node (ref "PCB2") (pin "A11") (pinfunction "A11_A11") (pintype "bidirectional"))
    )
    (net (code "106") (name "unconnected-(PCB2-PadA12)") (class "Default")
      (node (ref "PCB2") (pin "A12") (pinfunction "A12_A12") (pintype "bidirectional"))
    )
    (net (code "107") (name "unconnected-(PCB2-PadA13)") (class "Default")
      (node (ref "PCB2") (pin "A13") (pinfunction "A13_A13") (pintype "bidirectional"))
    )
    (net (code "108") (name "unconnected-(PCB2-PadA14)") (class "Default")
      (node (ref "PCB2") (pin "A14") (pinfunction "A14_A14") (pintype "bidirectional"))
    )
    (net (code "109") (name "unconnected-(PCB2-PadA15)") (class "Default")
      (node (ref "PCB2") (pin "A15") (pinfunction "A15_A15") (pintype "bidirectional"))
    )
    (net (code "110") (name "unconnected-(PCB2-PadGND__)") (class "Default")
      (node (ref "PCB2") (pin "GND__") (pinfunction "GND___GND__") (pintype "bidirectional"))
    )
    (net (code "111") (name "unconnected-(PCB2-PadMISO)") (class "Default")
      (node (ref "PCB2") (pin "MISO") (pinfunction "MISO_MISO") (pintype "bidirectional"))
    )
    (net (code "112") (name "unconnected-(PCB2-PadMOSI)") (class "Default")
      (node (ref "PCB2") (pin "MOSI") (pinfunction "MOSI_MOSI") (pintype "bidirectional"))
    )
    (net (code "113") (name "unconnected-(PCB2-PadRESET)") (class "Default")
      (node (ref "PCB2") (pin "RESET") (pinfunction "RESET_RESET") (pintype "bidirectional"))
    )
    (net (code "114") (name "unconnected-(PCB2-PadRESET.)") (class "Default")
      (node (ref "PCB2") (pin "RESET.") (pinfunction "RESET._RESET.") (pintype "bidirectional"))
    )
    (net (code "115") (name "unconnected-(PCB2-PadSCK)") (class "Default")
      (node (ref "PCB2") (pin "SCK") (pinfunction "SCK_SCK") (pintype "bidirectional"))
    )
    (net (code "116") (name "unconnected-(PCB2-PadSCL1)") (class "Default")
      (node (ref "PCB2") (pin "SCL1") (pinfunction "SCL1_SCL1") (pintype "bidirectional"))
    )
    (net (code "117") (name "unconnected-(PCB2-PadSDA1)") (class "Default")
      (node (ref "PCB2") (pin "SDA1") (pinfunction "SDA1_SDA1") (pintype "bidirectional"))
    )
  )
)
